# RPi_GPIO.net
KiCad netlist of a schematic drawn in EAGLE
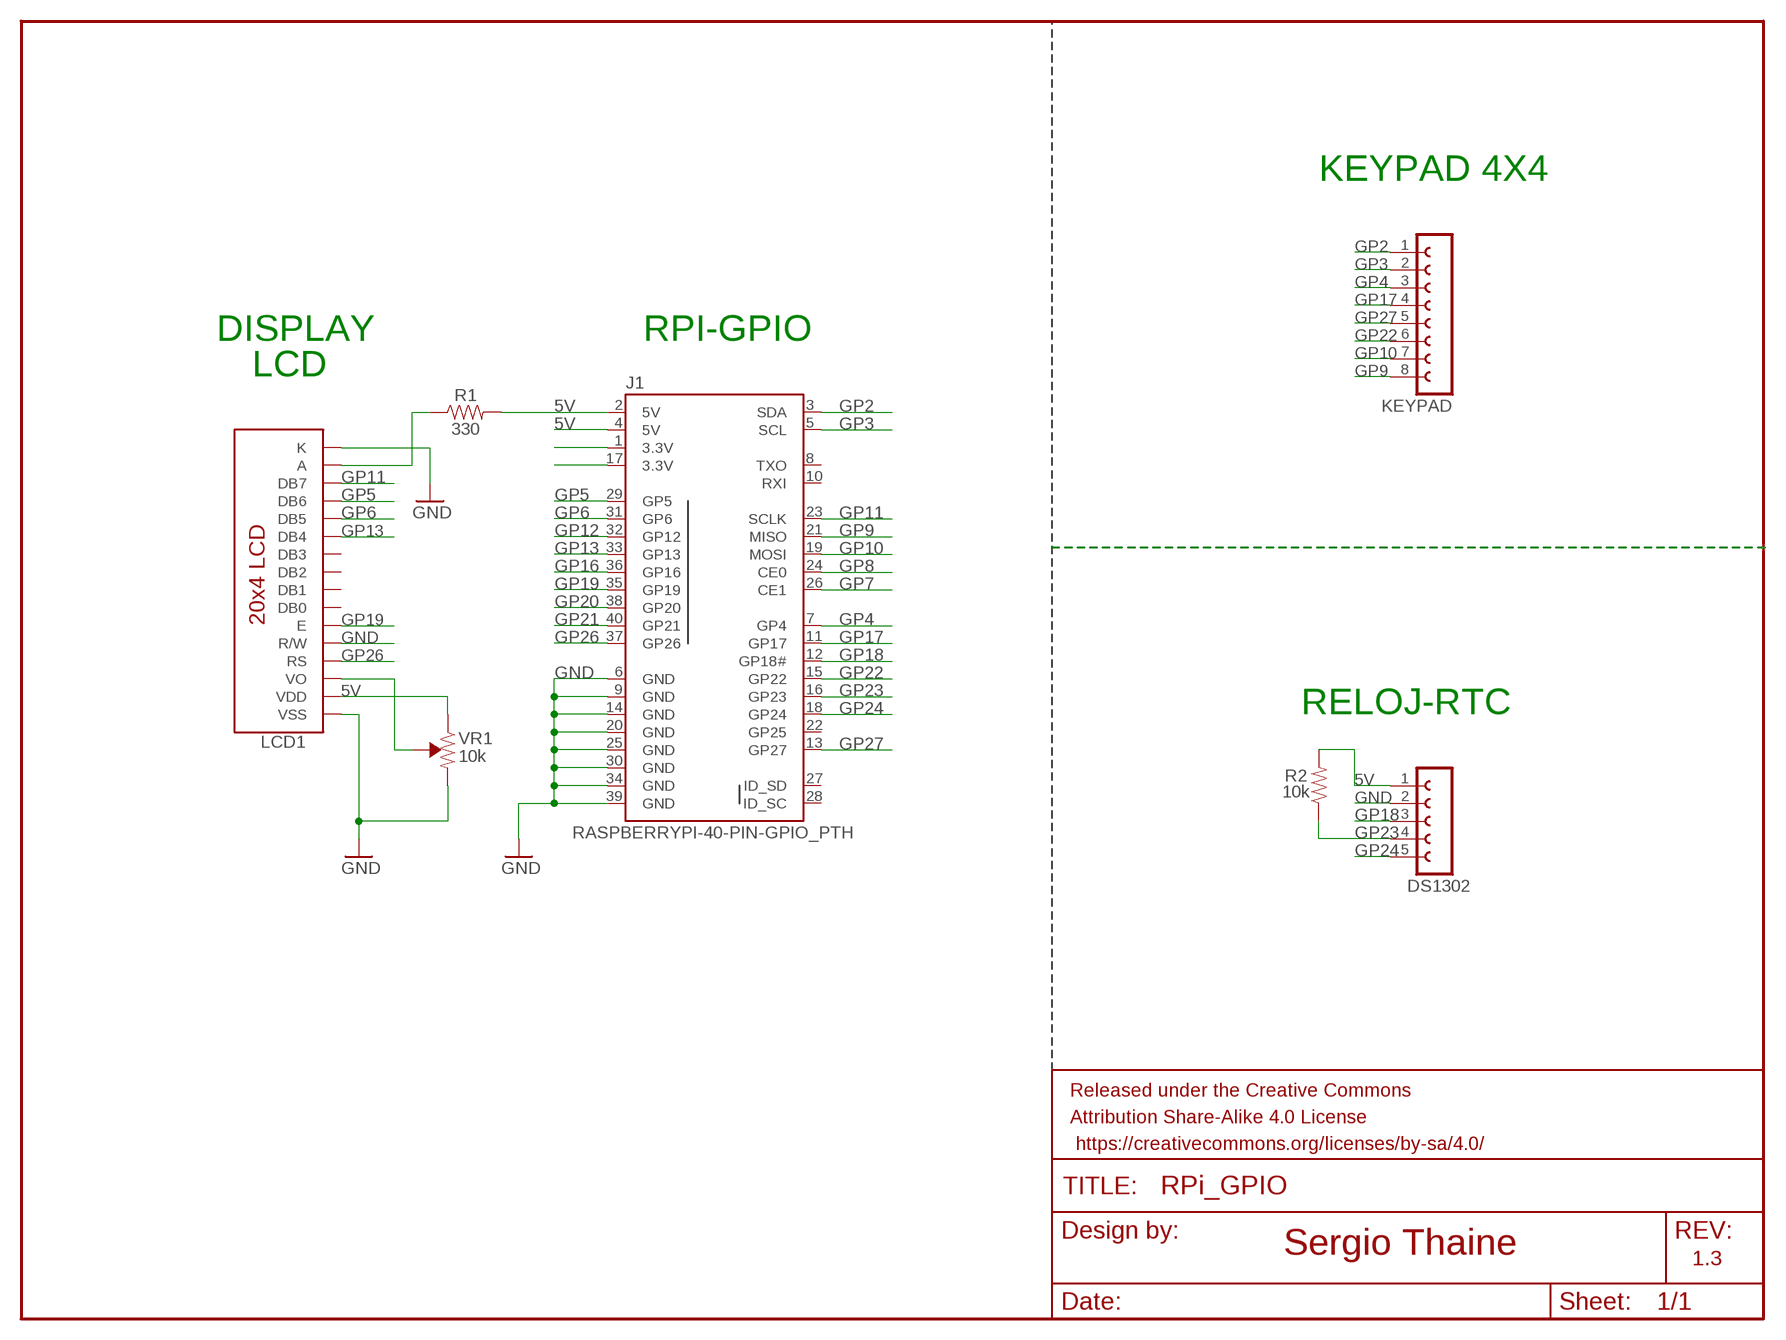
[diagram p0: schematic, sheet 1]

(export (version "E")
  (design (tool "Eeschema 10.0.6"))
  (components
    (comp (ref "DS1302")
      (value "FE05-1")
      (footprint "eagle-import:FE05-1")
      (libsource (lib "eagle-import") (part "FE05-1"))
    )
    (comp (ref "FRAME1")
      (value "FRAME-LETTERNO_PACKAGE")
      (footprint "eagle-import:DUMMY")
      (fields (field (name "DESIGNER") "Nobody"))
      (libsource (lib "eagle-import") (part "FRAME-LETTERNO_PACKAGE"))
    )
    (comp (ref "J1")
      (value "RASPBERRYPI-40-PIN-GPIO_PTH")
      (footprint "eagle-import:2X20_SHROUDED")
      (libsource (lib "eagle-import") (part "RASPBERRYPI-40-PIN-GPIO_PTH"))
    )
    (comp (ref "KEYPAD")
      (value "FE08-1")
      (footprint "eagle-import:FE08")
      (libsource (lib "eagle-import") (part "FE08-1"))
    )
    (comp (ref "LCD1")
      (value "LCD-16X2NOHOLES")
      (footprint "eagle-import:LCD-16X2_NOHOLESNOSILK")
      (libsource (lib "eagle-import") (part "LCD-16X2NOHOLES"))
    )
    (comp (ref "R1")
      (value "330")
      (footprint "eagle-import:AXIAL-0.3")
      (libsource (lib "eagle-import") (part "1KOHM-HORIZ-1/4W-1%"))
    )
    (comp (ref "R2")
      (value "10k")
      (footprint "eagle-import:AXIAL-0.3")
      (libsource (lib "eagle-import") (part "10KOHM-HORIZ-1/4W-1%"))
    )
    (comp (ref "VR1")
      (value "10k")
      (footprint "eagle-import:TRIMPOT-PTH-3386U")
      (libsource (lib "eagle-import") (part "TRIMPOT-PTH-10MM-KNOB-1/2W-10%"))
    )
  )
  (nets
    (net (code "1") (name "/5V") (class "Default")
      (node (ref "DS1302") (pin "1") (pinfunction "1_1") (pintype "passive"))
      (node (ref "J1") (pin "2") (pinfunction "5V_2") (pintype "power_in"))
      (node (ref "J1") (pin "4") (pinfunction "5V_4") (pintype "power_in"))
      (node (ref "LCD1") (pin "2") (pinfunction "VDD_2") (pintype "power_in"))
      (node (ref "R1") (pin "P$2") (pinfunction "2_P$2") (pintype "passive"))
      (node (ref "R2") (pin "P$2") (pinfunction "2_P$2") (pintype "passive"))
      (node (ref "VR1") (pin "3") (pinfunction "CW_3") (pintype "passive"))
    )
    (net (code "2") (name "/GP2") (class "Default")
      (node (ref "J1") (pin "3") (pinfunction "SDA_3") (pintype "bidirectional"))
      (node (ref "KEYPAD") (pin "1") (pinfunction "1_1") (pintype "passive"))
    )
    (net (code "3") (name "/GP3") (class "Default")
      (node (ref "J1") (pin "5") (pinfunction "SCL_5") (pintype "bidirectional"))
      (node (ref "KEYPAD") (pin "2") (pinfunction "2_2") (pintype "passive"))
    )
    (net (code "4") (name "/GP4") (class "Default")
      (node (ref "J1") (pin "7") (pinfunction "GP4_7") (pintype "bidirectional"))
      (node (ref "KEYPAD") (pin "3") (pinfunction "3_3") (pintype "passive"))
    )
    (net (code "5") (name "/GP5") (class "Default")
      (node (ref "J1") (pin "29") (pinfunction "GP5_29") (pintype "bidirectional"))
      (node (ref "LCD1") (pin "13") (pinfunction "DB6_13") (pintype "bidirectional"))
    )
    (net (code "6") (name "/GP6") (class "Default")
      (node (ref "J1") (pin "31") (pinfunction "GP6_31") (pintype "bidirectional"))
      (node (ref "LCD1") (pin "12") (pinfunction "DB5_12") (pintype "bidirectional"))
    )
    (net (code "7") (name "/GP7") (class "Default")
      (node (ref "J1") (pin "26") (pinfunction "CE1_26") (pintype "output"))
    )
    (net (code "8") (name "/GP8") (class "Default")
      (node (ref "J1") (pin "24") (pinfunction "CE0_24") (pintype "output"))
    )
    (net (code "9") (name "/GP9") (class "Default")
      (node (ref "J1") (pin "21") (pinfunction "MISO_21") (pintype "input"))
      (node (ref "KEYPAD") (pin "8") (pinfunction "8_8") (pintype "passive"))
    )
    (net (code "10") (name "/GP10") (class "Default")
      (node (ref "J1") (pin "19") (pinfunction "MOSI_19") (pintype "output"))
      (node (ref "KEYPAD") (pin "7") (pinfunction "7_7") (pintype "passive"))
    )
    (net (code "11") (name "/GP11") (class "Default")
      (node (ref "J1") (pin "23") (pinfunction "SCLK_23") (pintype "output"))
      (node (ref "LCD1") (pin "14") (pinfunction "DB7_14") (pintype "bidirectional"))
    )
    (net (code "12") (name "/GP12") (class "Default")
      (node (ref "J1") (pin "32") (pinfunction "GP12_32") (pintype "bidirectional"))
    )
    (net (code "13") (name "/GP13") (class "Default")
      (node (ref "J1") (pin "33") (pinfunction "GP13_33") (pintype "bidirectional"))
      (node (ref "LCD1") (pin "11") (pinfunction "DB4_11") (pintype "bidirectional"))
    )
    (net (code "14") (name "/GP16") (class "Default")
      (node (ref "J1") (pin "36") (pinfunction "GP16_36") (pintype "bidirectional"))
    )
    (net (code "15") (name "/GP17") (class "Default")
      (node (ref "J1") (pin "11") (pinfunction "GP17_11") (pintype "bidirectional"))
      (node (ref "KEYPAD") (pin "4") (pinfunction "4_4") (pintype "passive"))
    )
    (net (code "16") (name "/GP18") (class "Default")
      (node (ref "DS1302") (pin "3") (pinfunction "3_3") (pintype "passive"))
      (node (ref "J1") (pin "12") (pinfunction "GP18#_12") (pintype "bidirectional"))
    )
    (net (code "17") (name "/GP19") (class "Default")
      (node (ref "J1") (pin "35") (pinfunction "GP19_35") (pintype "bidirectional"))
      (node (ref "LCD1") (pin "6") (pinfunction "E_6") (pintype "input"))
    )
    (net (code "18") (name "/GP20") (class "Default")
      (node (ref "J1") (pin "38") (pinfunction "GP20_38") (pintype "bidirectional"))
    )
    (net (code "19") (name "/GP21") (class "Default")
      (node (ref "J1") (pin "40") (pinfunction "GP21_40") (pintype "bidirectional"))
    )
    (net (code "20") (name "/GP22") (class "Default")
      (node (ref "J1") (pin "15") (pinfunction "GP22_15") (pintype "bidirectional"))
      (node (ref "KEYPAD") (pin "6") (pinfunction "6_6") (pintype "passive"))
    )
    (net (code "21") (name "/GP23") (class "Default")
      (node (ref "DS1302") (pin "4") (pinfunction "4_4") (pintype "passive"))
      (node (ref "J1") (pin "16") (pinfunction "GP23_16") (pintype "bidirectional"))
      (node (ref "R2") (pin "P$1") (pinfunction "1_P$1") (pintype "passive"))
    )
    (net (code "22") (name "/GP24") (class "Default")
      (node (ref "DS1302") (pin "5") (pinfunction "5_5") (pintype "passive"))
      (node (ref "J1") (pin "18") (pinfunction "GP24_18") (pintype "bidirectional"))
    )
    (net (code "23") (name "/GP26") (class "Default")
      (node (ref "J1") (pin "37") (pinfunction "GP26_37") (pintype "bidirectional"))
      (node (ref "LCD1") (pin "4") (pinfunction "RS_4") (pintype "input"))
    )
    (net (code "24") (name "/GP27") (class "Default")
      (node (ref "J1") (pin "13") (pinfunction "GP27_13") (pintype "bidirectional"))
      (node (ref "KEYPAD") (pin "5") (pinfunction "5_5") (pintype "passive"))
    )
    (net (code "25") (name "GND") (class "Default")
      (node (ref "DS1302") (pin "2") (pinfunction "2_2") (pintype "passive"))
      (node (ref "J1") (pin "14") (pinfunction "GND_14") (pintype "power_in"))
      (node (ref "J1") (pin "20") (pinfunction "GND_20") (pintype "power_in"))
      (node (ref "J1") (pin "25") (pinfunction "GND_25") (pintype "power_in"))
      (node (ref "J1") (pin "30") (pinfunction "GND_30") (pintype "power_in"))
      (node (ref "J1") (pin "34") (pinfunction "GND_34") (pintype "power_in"))
      (node (ref "J1") (pin "39") (pinfunction "GND_39") (pintype "power_in"))
      (node (ref "J1") (pin "6") (pinfunction "GND_6") (pintype "power_in"))
      (node (ref "J1") (pin "9") (pinfunction "GND_9") (pintype "power_in"))
      (node (ref "LCD1") (pin "1") (pinfunction "VSS_1") (pintype "power_in"))
      (node (ref "LCD1") (pin "16") (pinfunction "K_16") (pintype "power_in"))
      (node (ref "LCD1") (pin "5") (pinfunction "R/W_5") (pintype "input"))
      (node (ref "VR1") (pin "1") (pinfunction "CCW_1") (pintype "passive"))
    )
    (net (code "26") (name "Net-(LCD1-A)") (class "Default")
      (node (ref "LCD1") (pin "15") (pinfunction "A_15") (pintype "power_in"))
      (node (ref "R1") (pin "P$1") (pinfunction "1_P$1") (pintype "passive"))
    )
    (net (code "27") (name "Net-(LCD1-VO)") (class "Default")
      (node (ref "LCD1") (pin "3") (pinfunction "VO_3") (pintype "bidirectional"))
      (node (ref "VR1") (pin "2") (pinfunction "WIPER_2") (pintype "passive"))
    )
    (net (code "28") (name "unconnected-(J1-3.3V-Pad1)") (class "Default")
      (node (ref "J1") (pin "1") (pinfunction "3.3V_1") (pintype "power_in"))
    )
    (net (code "29") (name "unconnected-(J1-3.3V-Pad17)") (class "Default")
      (node (ref "J1") (pin "17") (pinfunction "3.3V_17") (pintype "power_in"))
    )
    (net (code "30") (name "unconnected-(J1-GP25-Pad22)") (class "Default")
      (node (ref "J1") (pin "22") (pinfunction "GP25_22") (pintype "bidirectional"))
    )
    (net (code "31") (name "unconnected-(J1-ID_SC-Pad28)") (class "Default")
      (node (ref "J1") (pin "28") (pinfunction "ID_SC_28") (pintype "bidirectional"))
    )
    (net (code "32") (name "unconnected-(J1-ID_SD-Pad27)") (class "Default")
      (node (ref "J1") (pin "27") (pinfunction "ID_SD_27") (pintype "bidirectional"))
    )
    (net (code "33") (name "unconnected-(J1-RXI-Pad10)") (class "Default")
      (node (ref "J1") (pin "10") (pinfunction "RXI_10") (pintype "input"))
    )
    (net (code "34") (name "unconnected-(J1-TXO-Pad8)") (class "Default")
      (node (ref "J1") (pin "8") (pinfunction "TXO_8") (pintype "output"))
    )
    (net (code "35") (name "unconnected-(LCD1-DB0-Pad7)") (class "Default")
      (node (ref "LCD1") (pin "7") (pinfunction "DB0_7") (pintype "bidirectional"))
    )
    (net (code "36") (name "unconnected-(LCD1-DB1-Pad8)") (class "Default")
      (node (ref "LCD1") (pin "8") (pinfunction "DB1_8") (pintype "bidirectional"))
    )
    (net (code "37") (name "unconnected-(LCD1-DB2-Pad9)") (class "Default")
      (node (ref "LCD1") (pin "9") (pinfunction "DB2_9") (pintype "bidirectional"))
    )
    (net (code "38") (name "unconnected-(LCD1-DB3-Pad10)") (class "Default")
      (node (ref "LCD1") (pin "10") (pinfunction "DB3_10") (pintype "bidirectional"))
    )
  )
)
